# v1.net
KiCad netlist of a schematic drawn in EAGLE
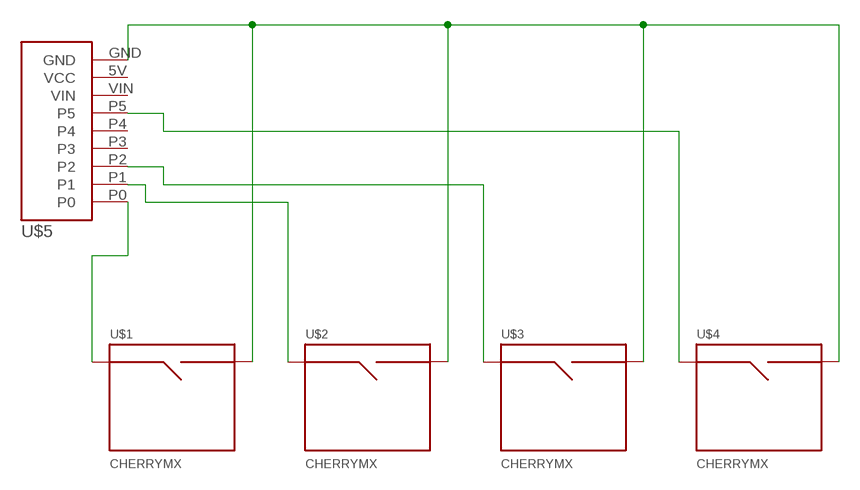
[diagram p0: schematic, sheet 1]

(export (version "E")
  (design (tool "Eeschema 10.0.6"))
  (components
    (comp (ref "U$1")
      (value "CHERRYMX")
      (footprint "eagle-import:CHERRYMX")
      (libsource (lib "eagle-import") (part "CHERRYMX"))
    )
    (comp (ref "U$2")
      (value "CHERRYMX")
      (footprint "eagle-import:CHERRYMX")
      (libsource (lib "eagle-import") (part "CHERRYMX"))
    )
    (comp (ref "U$3")
      (value "CHERRYMX")
      (footprint "eagle-import:CHERRYMX")
      (libsource (lib "eagle-import") (part "CHERRYMX"))
    )
    (comp (ref "U$4")
      (value "CHERRYMX")
      (footprint "eagle-import:CHERRYMX")
      (libsource (lib "eagle-import") (part "CHERRYMX"))
    )
    (comp (ref "U$5")
      (value "ATTINY85")
      (footprint "eagle-import:ATTINY85")
      (libsource (lib "eagle-import") (part "ATTINY85"))
    )
  )
  (nets
    (net (code "1") (name "Net-(U$1-SIG1)") (class "Default")
      (node (ref "U$1") (pin "P$1") (pinfunction "SIG1_P$1") (pintype "bidirectional"))
      (node (ref "U$5") (pin "P0") (pinfunction "P0_P0") (pintype "bidirectional"))
    )
    (net (code "2") (name "Net-(U$1-SIG2)") (class "Default")
      (node (ref "U$1") (pin "P$2") (pinfunction "SIG2_P$2") (pintype "bidirectional"))
      (node (ref "U$2") (pin "P$2") (pinfunction "SIG2_P$2") (pintype "bidirectional"))
      (node (ref "U$3") (pin "P$2") (pinfunction "SIG2_P$2") (pintype "bidirectional"))
      (node (ref "U$4") (pin "P$2") (pinfunction "SIG2_P$2") (pintype "bidirectional"))
      (node (ref "U$5") (pin "GND") (pinfunction "GND_GND") (pintype "bidirectional"))
    )
    (net (code "3") (name "Net-(U$2-SIG1)") (class "Default")
      (node (ref "U$2") (pin "P$1") (pinfunction "SIG1_P$1") (pintype "bidirectional"))
      (node (ref "U$5") (pin "P1") (pinfunction "P1_P1") (pintype "bidirectional"))
    )
    (net (code "4") (name "Net-(U$3-SIG1)") (class "Default")
      (node (ref "U$3") (pin "P$1") (pinfunction "SIG1_P$1") (pintype "bidirectional"))
      (node (ref "U$5") (pin "P2") (pinfunction "P2_P2") (pintype "bidirectional"))
    )
    (net (code "5") (name "Net-(U$4-SIG1)") (class "Default")
      (node (ref "U$4") (pin "P$1") (pinfunction "SIG1_P$1") (pintype "bidirectional"))
      (node (ref "U$5") (pin "P5") (pinfunction "P5_P5") (pintype "bidirectional"))
    )
    (net (code "6") (name "unconnected-(U$5-PadP3)") (class "Default")
      (node (ref "U$5") (pin "P3") (pinfunction "P3_P3") (pintype "bidirectional"))
    )
    (net (code "7") (name "unconnected-(U$5-PadP4)") (class "Default")
      (node (ref "U$5") (pin "P4") (pinfunction "P4_P4") (pintype "bidirectional"))
    )
    (net (code "8") (name "unconnected-(U$5-PadVIN)") (class "Default")
      (node (ref "U$5") (pin "VIN") (pinfunction "VIN_VIN") (pintype "bidirectional"))
    )
    (net (code "9") (name "unconnected-(U$5-VCC-Pad5V)") (class "Default")
      (node (ref "U$5") (pin "5V") (pinfunction "VCC_5V") (pintype "bidirectional"))
    )
  )
)
